# Light_Sensos.net
KiCad netlist of a schematic drawn in EAGLE
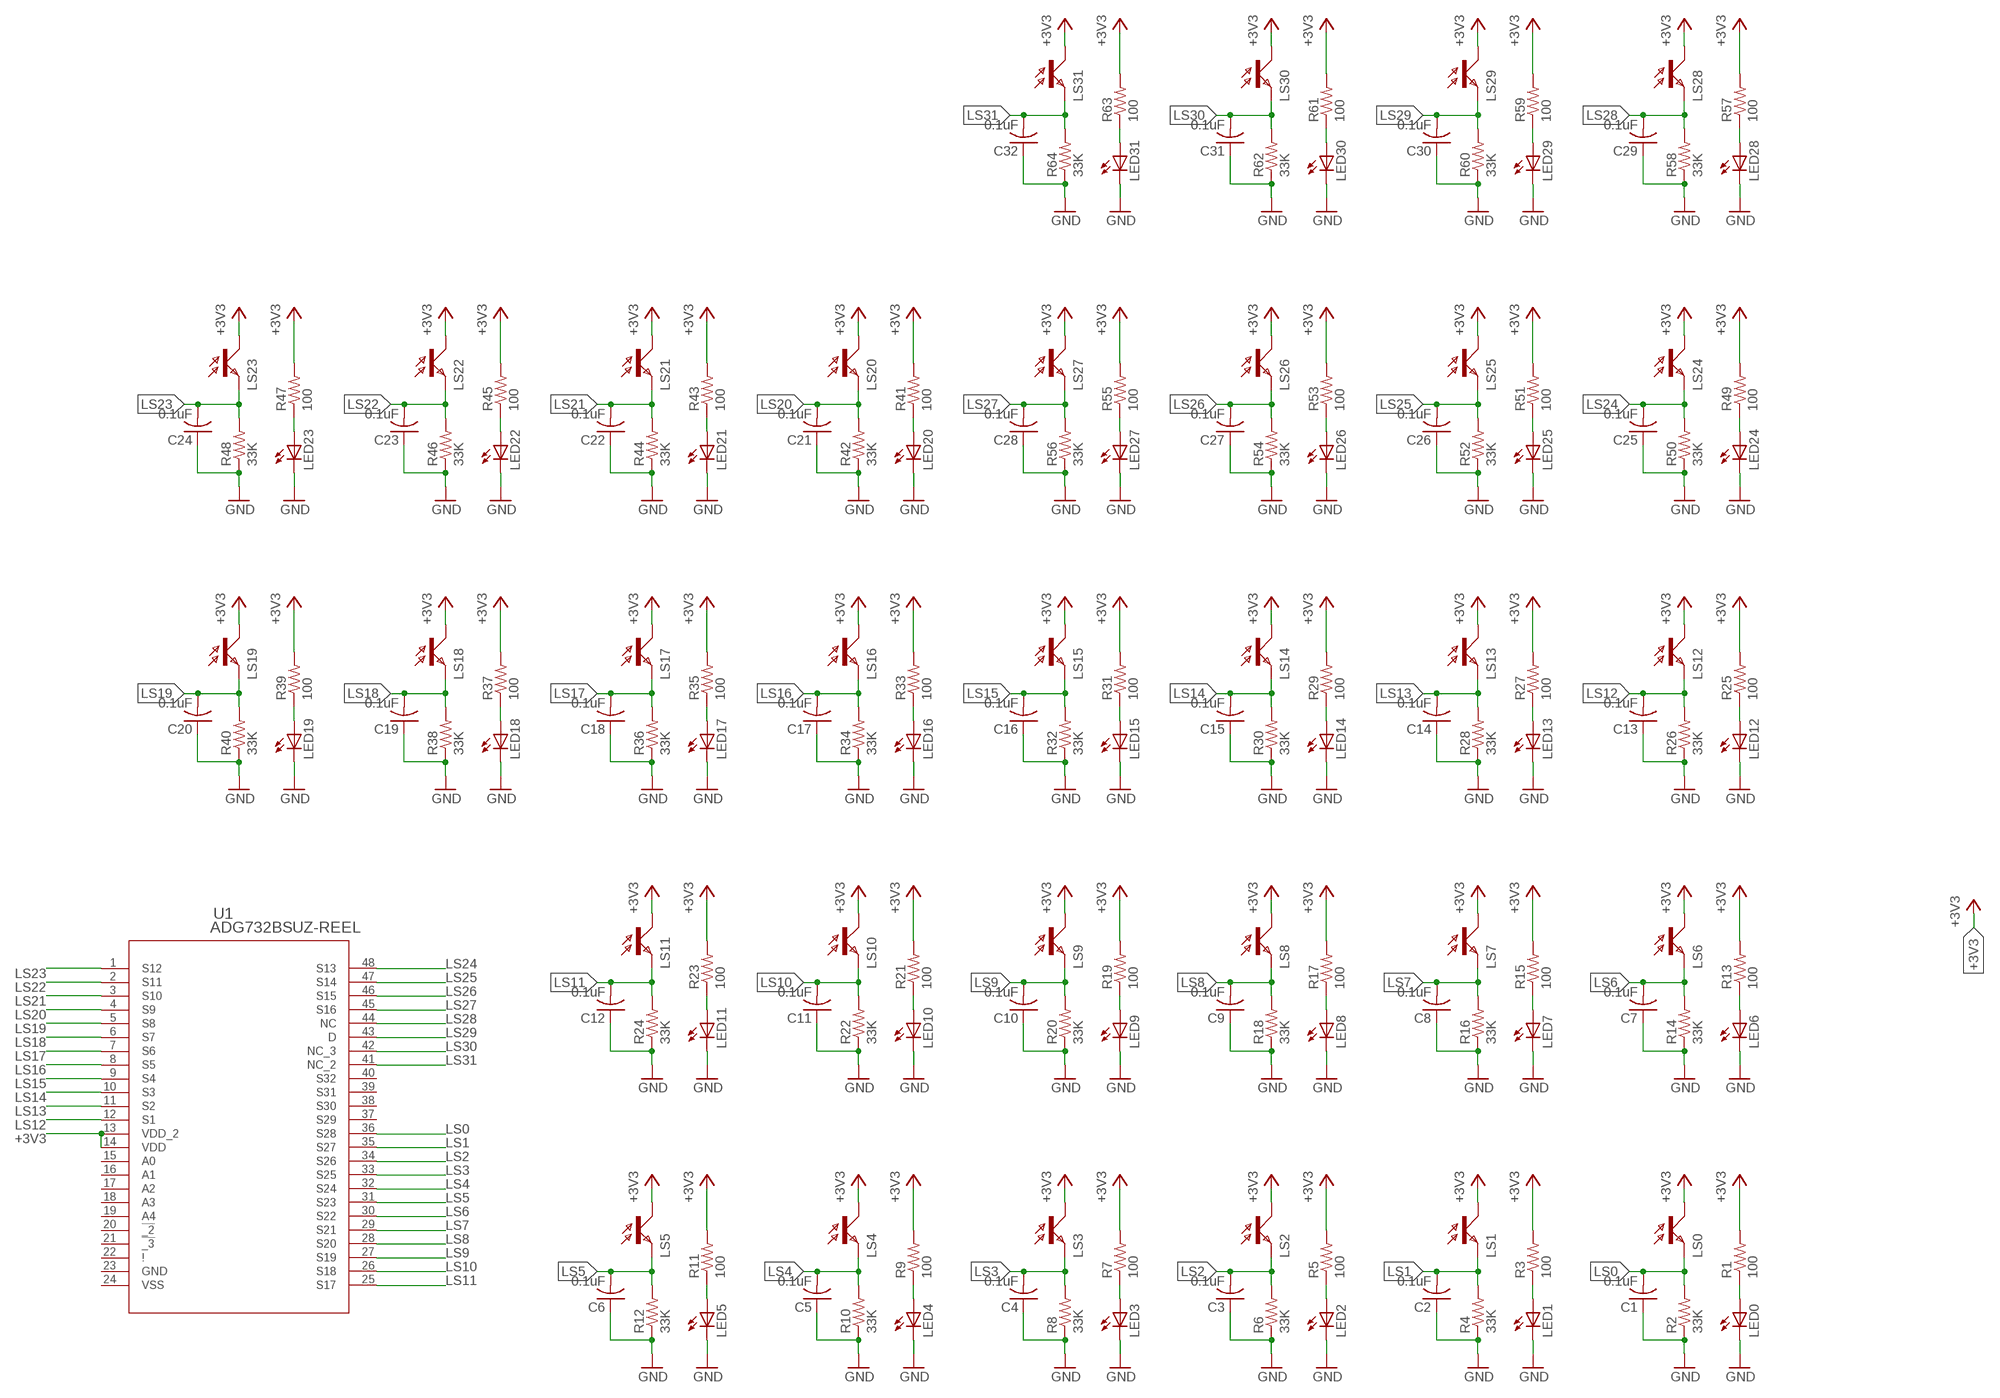
[diagram p0: schematic, sheet 1]

(export (version "E")
  (design (tool "Eeschema 10.0.6"))
  (components
    (comp (ref "C1")
      (value "0.1uF")
      (footprint "eagle-import:C0603")
      (libsource (lib "eagle-import") (part "C-USC0603"))
    )
    (comp (ref "C2")
      (value "0.1uF")
      (footprint "eagle-import:C0603")
      (libsource (lib "eagle-import") (part "C-USC0603"))
    )
    (comp (ref "C3")
      (value "0.1uF")
      (footprint "eagle-import:C0603")
      (libsource (lib "eagle-import") (part "C-USC0603"))
    )
    (comp (ref "C4")
      (value "0.1uF")
      (footprint "eagle-import:C0603")
      (libsource (lib "eagle-import") (part "C-USC0603"))
    )
    (comp (ref "C5")
      (value "0.1uF")
      (footprint "eagle-import:C0603")
      (libsource (lib "eagle-import") (part "C-USC0603"))
    )
    (comp (ref "C6")
      (value "0.1uF")
      (footprint "eagle-import:C0603")
      (libsource (lib "eagle-import") (part "C-USC0603"))
    )
    (comp (ref "C7")
      (value "0.1uF")
      (footprint "eagle-import:C0603")
      (libsource (lib "eagle-import") (part "C-USC0603"))
    )
    (comp (ref "C8")
      (value "0.1uF")
      (footprint "eagle-import:C0603")
      (libsource (lib "eagle-import") (part "C-USC0603"))
    )
    (comp (ref "C9")
      (value "0.1uF")
      (footprint "eagle-import:C0603")
      (libsource (lib "eagle-import") (part "C-USC0603"))
    )
    (comp (ref "C10")
      (value "0.1uF")
      (footprint "eagle-import:C0603")
      (libsource (lib "eagle-import") (part "C-USC0603"))
    )
    (comp (ref "C11")
      (value "0.1uF")
      (footprint "eagle-import:C0603")
      (libsource (lib "eagle-import") (part "C-USC0603"))
    )
    (comp (ref "C12")
      (value "0.1uF")
      (footprint "eagle-import:C0603")
      (libsource (lib "eagle-import") (part "C-USC0603"))
    )
    (comp (ref "C13")
      (value "0.1uF")
      (footprint "eagle-import:C0603")
      (libsource (lib "eagle-import") (part "C-USC0603"))
    )
    (comp (ref "C14")
      (value "0.1uF")
      (footprint "eagle-import:C0603")
      (libsource (lib "eagle-import") (part "C-USC0603"))
    )
    (comp (ref "C15")
      (value "0.1uF")
      (footprint "eagle-import:C0603")
      (libsource (lib "eagle-import") (part "C-USC0603"))
    )
    (comp (ref "C16")
      (value "0.1uF")
      (footprint "eagle-import:C0603")
      (libsource (lib "eagle-import") (part "C-USC0603"))
    )
    (comp (ref "C17")
      (value "0.1uF")
      (footprint "eagle-import:C0603")
      (libsource (lib "eagle-import") (part "C-USC0603"))
    )
    (comp (ref "C18")
      (value "0.1uF")
      (footprint "eagle-import:C0603")
      (libsource (lib "eagle-import") (part "C-USC0603"))
    )
    (comp (ref "C19")
      (value "0.1uF")
      (footprint "eagle-import:C0603")
      (libsource (lib "eagle-import") (part "C-USC0603"))
    )
    (comp (ref "C20")
      (value "0.1uF")
      (footprint "eagle-import:C0603")
      (libsource (lib "eagle-import") (part "C-USC0603"))
    )
    (comp (ref "C21")
      (value "0.1uF")
      (footprint "eagle-import:C0603")
      (libsource (lib "eagle-import") (part "C-USC0603"))
    )
    (comp (ref "C22")
      (value "0.1uF")
      (footprint "eagle-import:C0603")
      (libsource (lib "eagle-import") (part "C-USC0603"))
    )
    (comp (ref "C23")
      (value "0.1uF")
      (footprint "eagle-import:C0603")
      (libsource (lib "eagle-import") (part "C-USC0603"))
    )
    (comp (ref "C24")
      (value "0.1uF")
      (footprint "eagle-import:C0603")
      (libsource (lib "eagle-import") (part "C-USC0603"))
    )
    (comp (ref "C25")
      (value "0.1uF")
      (footprint "eagle-import:C0603")
      (libsource (lib "eagle-import") (part "C-USC0603"))
    )
    (comp (ref "C26")
      (value "0.1uF")
      (footprint "eagle-import:C0603")
      (libsource (lib "eagle-import") (part "C-USC0603"))
    )
    (comp (ref "C27")
      (value "0.1uF")
      (footprint "eagle-import:C0603")
      (libsource (lib "eagle-import") (part "C-USC0603"))
    )
    (comp (ref "C28")
      (value "0.1uF")
      (footprint "eagle-import:C0603")
      (libsource (lib "eagle-import") (part "C-USC0603"))
    )
    (comp (ref "C29")
      (value "0.1uF")
      (footprint "eagle-import:C0603")
      (libsource (lib "eagle-import") (part "C-USC0603"))
    )
    (comp (ref "C30")
      (value "0.1uF")
      (footprint "eagle-import:C0603")
      (libsource (lib "eagle-import") (part "C-USC0603"))
    )
    (comp (ref "C31")
      (value "0.1uF")
      (footprint "eagle-import:C0603")
      (libsource (lib "eagle-import") (part "C-USC0603"))
    )
    (comp (ref "C32")
      (value "0.1uF")
      (footprint "eagle-import:C0603")
      (libsource (lib "eagle-import") (part "C-USC0603"))
    )
    (comp (ref "LED0")
      (value "LEDCHIPLED_0603")
      (footprint "eagle-import:CHIPLED_0603")
      (libsource (lib "eagle-import") (part "LEDCHIPLED_0603"))
    )
    (comp (ref "LED1")
      (value "LEDCHIPLED_0603")
      (footprint "eagle-import:CHIPLED_0603")
      (libsource (lib "eagle-import") (part "LEDCHIPLED_0603"))
    )
    (comp (ref "LED2")
      (value "LEDCHIPLED_0603")
      (footprint "eagle-import:CHIPLED_0603")
      (libsource (lib "eagle-import") (part "LEDCHIPLED_0603"))
    )
    (comp (ref "LED3")
      (value "LEDCHIPLED_0603")
      (footprint "eagle-import:CHIPLED_0603")
      (libsource (lib "eagle-import") (part "LEDCHIPLED_0603"))
    )
    (comp (ref "LED4")
      (value "LEDCHIPLED_0603")
      (footprint "eagle-import:CHIPLED_0603")
      (libsource (lib "eagle-import") (part "LEDCHIPLED_0603"))
    )
    (comp (ref "LED5")
      (value "LEDCHIPLED_0603")
      (footprint "eagle-import:CHIPLED_0603")
      (libsource (lib "eagle-import") (part "LEDCHIPLED_0603"))
    )
    (comp (ref "LED6")
      (value "LEDCHIPLED_0603")
      (footprint "eagle-import:CHIPLED_0603")
      (libsource (lib "eagle-import") (part "LEDCHIPLED_0603"))
    )
    (comp (ref "LED7")
      (value "LEDCHIPLED_0603")
      (footprint "eagle-import:CHIPLED_0603")
      (libsource (lib "eagle-import") (part "LEDCHIPLED_0603"))
    )
    (comp (ref "LED8")
      (value "LEDCHIPLED_0603")
      (footprint "eagle-import:CHIPLED_0603")
      (libsource (lib "eagle-import") (part "LEDCHIPLED_0603"))
    )
    (comp (ref "LED9")
      (value "LEDCHIPLED_0603")
      (footprint "eagle-import:CHIPLED_0603")
      (libsource (lib "eagle-import") (part "LEDCHIPLED_0603"))
    )
    (comp (ref "LED10")
      (value "LEDCHIPLED_0603")
      (footprint "eagle-import:CHIPLED_0603")
      (libsource (lib "eagle-import") (part "LEDCHIPLED_0603"))
    )
    (comp (ref "LED11")
      (value "LEDCHIPLED_0603")
      (footprint "eagle-import:CHIPLED_0603")
      (libsource (lib "eagle-import") (part "LEDCHIPLED_0603"))
    )
    (comp (ref "LED12")
      (value "LEDCHIPLED_0603")
      (footprint "eagle-import:CHIPLED_0603")
      (libsource (lib "eagle-import") (part "LEDCHIPLED_0603"))
    )
    (comp (ref "LED13")
      (value "LEDCHIPLED_0603")
      (footprint "eagle-import:CHIPLED_0603")
      (libsource (lib "eagle-import") (part "LEDCHIPLED_0603"))
    )
    (comp (ref "LED14")
      (value "LEDCHIPLED_0603")
      (footprint "eagle-import:CHIPLED_0603")
      (libsource (lib "eagle-import") (part "LEDCHIPLED_0603"))
    )
    (comp (ref "LED15")
      (value "LEDCHIPLED_0603")
      (footprint "eagle-import:CHIPLED_0603")
      (libsource (lib "eagle-import") (part "LEDCHIPLED_0603"))
    )
    (comp (ref "LED16")
      (value "LEDCHIPLED_0603")
      (footprint "eagle-import:CHIPLED_0603")
      (libsource (lib "eagle-import") (part "LEDCHIPLED_0603"))
    )
    (comp (ref "LED17")
      (value "LEDCHIPLED_0603")
      (footprint "eagle-import:CHIPLED_0603")
      (libsource (lib "eagle-import") (part "LEDCHIPLED_0603"))
    )
    (comp (ref "LED18")
      (value "LEDCHIPLED_0603")
      (footprint "eagle-import:CHIPLED_0603")
      (libsource (lib "eagle-import") (part "LEDCHIPLED_0603"))
    )
    (comp (ref "LED19")
      (value "LEDCHIPLED_0603")
      (footprint "eagle-import:CHIPLED_0603")
      (libsource (lib "eagle-import") (part "LEDCHIPLED_0603"))
    )
    (comp (ref "LED20")
      (value "LEDCHIPLED_0603")
      (footprint "eagle-import:CHIPLED_0603")
      (libsource (lib "eagle-import") (part "LEDCHIPLED_0603"))
    )
    (comp (ref "LED21")
      (value "LEDCHIPLED_0603")
      (footprint "eagle-import:CHIPLED_0603")
      (libsource (lib "eagle-import") (part "LEDCHIPLED_0603"))
    )
    (comp (ref "LED22")
      (value "LEDCHIPLED_0603")
      (footprint "eagle-import:CHIPLED_0603")
      (libsource (lib "eagle-import") (part "LEDCHIPLED_0603"))
    )
    (comp (ref "LED23")
      (value "LEDCHIPLED_0603")
      (footprint "eagle-import:CHIPLED_0603")
      (libsource (lib "eagle-import") (part "LEDCHIPLED_0603"))
    )
    (comp (ref "LED24")
      (value "LEDCHIPLED_0603")
      (footprint "eagle-import:CHIPLED_0603")
      (libsource (lib "eagle-import") (part "LEDCHIPLED_0603"))
    )
    (comp (ref "LED25")
      (value "LEDCHIPLED_0603")
      (footprint "eagle-import:CHIPLED_0603")
      (libsource (lib "eagle-import") (part "LEDCHIPLED_0603"))
    )
    (comp (ref "LED26")
      (value "LEDCHIPLED_0603")
      (footprint "eagle-import:CHIPLED_0603")
      (libsource (lib "eagle-import") (part "LEDCHIPLED_0603"))
    )
    (comp (ref "LED27")
      (value "LEDCHIPLED_0603")
      (footprint "eagle-import:CHIPLED_0603")
      (libsource (lib "eagle-import") (part "LEDCHIPLED_0603"))
    )
    (comp (ref "LED28")
      (value "LEDCHIPLED_0603")
      (footprint "eagle-import:CHIPLED_0603")
      (libsource (lib "eagle-import") (part "LEDCHIPLED_0603"))
    )
    (comp (ref "LED29")
      (value "LEDCHIPLED_0603")
      (footprint "eagle-import:CHIPLED_0603")
      (libsource (lib "eagle-import") (part "LEDCHIPLED_0603"))
    )
    (comp (ref "LED30")
      (value "LEDCHIPLED_0603")
      (footprint "eagle-import:CHIPLED_0603")
      (libsource (lib "eagle-import") (part "LEDCHIPLED_0603"))
    )
    (comp (ref "LED31")
      (value "LEDCHIPLED_0603")
      (footprint "eagle-import:CHIPLED_0603")
      (libsource (lib "eagle-import") (part "LEDCHIPLED_0603"))
    )
    (comp (ref "LS0")
      (value "ALS")
      (footprint "eagle-import:SMD")
      (libsource (lib "eagle-import") (part "ALS"))
    )
    (comp (ref "LS1")
      (value "ALS")
      (footprint "eagle-import:SMD")
      (libsource (lib "eagle-import") (part "ALS"))
    )
    (comp (ref "LS2")
      (value "ALS")
      (footprint "eagle-import:SMD")
      (libsource (lib "eagle-import") (part "ALS"))
    )
    (comp (ref "LS3")
      (value "ALS")
      (footprint "eagle-import:SMD")
      (libsource (lib "eagle-import") (part "ALS"))
    )
    (comp (ref "LS4")
      (value "ALS")
      (footprint "eagle-import:SMD")
      (libsource (lib "eagle-import") (part "ALS"))
    )
    (comp (ref "LS5")
      (value "ALS")
      (footprint "eagle-import:SMD")
      (libsource (lib "eagle-import") (part "ALS"))
    )
    (comp (ref "LS6")
      (value "ALS")
      (footprint "eagle-import:SMD")
      (libsource (lib "eagle-import") (part "ALS"))
    )
    (comp (ref "LS7")
      (value "ALS")
      (footprint "eagle-import:SMD")
      (libsource (lib "eagle-import") (part "ALS"))
    )
    (comp (ref "LS8")
      (value "ALS")
      (footprint "eagle-import:SMD")
      (libsource (lib "eagle-import") (part "ALS"))
    )
    (comp (ref "LS9")
      (value "ALS")
      (footprint "eagle-import:SMD")
      (libsource (lib "eagle-import") (part "ALS"))
    )
    (comp (ref "LS10")
      (value "ALS")
      (footprint "eagle-import:SMD")
      (libsource (lib "eagle-import") (part "ALS"))
    )
    (comp (ref "LS11")
      (value "ALS")
      (footprint "eagle-import:SMD")
      (libsource (lib "eagle-import") (part "ALS"))
    )
    (comp (ref "LS12")
      (value "ALS")
      (footprint "eagle-import:SMD")
      (libsource (lib "eagle-import") (part "ALS"))
    )
    (comp (ref "LS13")
      (value "ALS")
      (footprint "eagle-import:SMD")
      (libsource (lib "eagle-import") (part "ALS"))
    )
    (comp (ref "LS14")
      (value "ALS")
      (footprint "eagle-import:SMD")
      (libsource (lib "eagle-import") (part "ALS"))
    )
    (comp (ref "LS15")
      (value "ALS")
      (footprint "eagle-import:SMD")
      (libsource (lib "eagle-import") (part "ALS"))
    )
    (comp (ref "LS16")
      (value "ALS")
      (footprint "eagle-import:SMD")
      (libsource (lib "eagle-import") (part "ALS"))
    )
    (comp (ref "LS17")
      (value "ALS")
      (footprint "eagle-import:SMD")
      (libsource (lib "eagle-import") (part "ALS"))
    )
    (comp (ref "LS18")
      (value "ALS")
      (footprint "eagle-import:SMD")
      (libsource (lib "eagle-import") (part "ALS"))
    )
    (comp (ref "LS19")
      (value "ALS")
      (footprint "eagle-import:SMD")
      (libsource (lib "eagle-import") (part "ALS"))
    )
    (comp (ref "LS20")
      (value "ALS")
      (footprint "eagle-import:SMD")
      (libsource (lib "eagle-import") (part "ALS"))
    )
    (comp (ref "LS21")
      (value "ALS")
      (footprint "eagle-import:SMD")
      (libsource (lib "eagle-import") (part "ALS"))
    )
    (comp (ref "LS22")
      (value "ALS")
      (footprint "eagle-import:SMD")
      (libsource (lib "eagle-import") (part "ALS"))
    )
    (comp (ref "LS23")
      (value "ALS")
      (footprint "eagle-import:SMD")
      (libsource (lib "eagle-import") (part "ALS"))
    )
    (comp (ref "LS24")
      (value "ALS")
      (footprint "eagle-import:SMD")
      (libsource (lib "eagle-import") (part "ALS"))
    )
    (comp (ref "LS25")
      (value "ALS")
      (footprint "eagle-import:SMD")
      (libsource (lib "eagle-import") (part "ALS"))
    )
    (comp (ref "LS26")
      (value "ALS")
      (footprint "eagle-import:SMD")
      (libsource (lib "eagle-import") (part "ALS"))
    )
    (comp (ref "LS27")
      (value "ALS")
      (footprint "eagle-import:SMD")
      (libsource (lib "eagle-import") (part "ALS"))
    )
    (comp (ref "LS28")
      (value "ALS")
      (footprint "eagle-import:SMD")
      (libsource (lib "eagle-import") (part "ALS"))
    )
    (comp (ref "LS29")
      (value "ALS")
      (footprint "eagle-import:SMD")
      (libsource (lib "eagle-import") (part "ALS"))
    )
    (comp (ref "LS30")
      (value "ALS")
      (footprint "eagle-import:SMD")
      (libsource (lib "eagle-import") (part "ALS"))
    )
    (comp (ref "LS31")
      (value "ALS")
      (footprint "eagle-import:SMD")
      (libsource (lib "eagle-import") (part "ALS"))
    )
    (comp (ref "R1")
      (value "100")
      (footprint "eagle-import:R0603")
      (libsource (lib "eagle-import") (part "R-US_R0603"))
    )
    (comp (ref "R2")
      (value "33K")
      (footprint "eagle-import:R0603")
      (libsource (lib "eagle-import") (part "R-US_R0603"))
    )
    (comp (ref "R3")
      (value "100")
      (footprint "eagle-import:R0603")
      (libsource (lib "eagle-import") (part "R-US_R0603"))
    )
    (comp (ref "R4")
      (value "33K")
      (footprint "eagle-import:R0603")
      (libsource (lib "eagle-import") (part "R-US_R0603"))
    )
    (comp (ref "R5")
      (value "100")
      (footprint "eagle-import:R0603")
      (libsource (lib "eagle-import") (part "R-US_R0603"))
    )
    (comp (ref "R6")
      (value "33K")
      (footprint "eagle-import:R0603")
      (libsource (lib "eagle-import") (part "R-US_R0603"))
    )
    (comp (ref "R7")
      (value "100")
      (footprint "eagle-import:R0603")
      (libsource (lib "eagle-import") (part "R-US_R0603"))
    )
    (comp (ref "R8")
      (value "33K")
      (footprint "eagle-import:R0603")
      (libsource (lib "eagle-import") (part "R-US_R0603"))
    )
    (comp (ref "R9")
      (value "100")
      (footprint "eagle-import:R0603")
      (libsource (lib "eagle-import") (part "R-US_R0603"))
    )
    (comp (ref "R10")
      (value "33K")
      (footprint "eagle-import:R0603")
      (libsource (lib "eagle-import") (part "R-US_R0603"))
    )
    (comp (ref "R11")
      (value "100")
      (footprint "eagle-import:R0603")
      (libsource (lib "eagle-import") (part "R-US_R0603"))
    )
    (comp (ref "R12")
      (value "33K")
      (footprint "eagle-import:R0603")
      (libsource (lib "eagle-import") (part "R-US_R0603"))
    )
    (comp (ref "R13")
      (value "100")
      (footprint "eagle-import:R0603")
      (libsource (lib "eagle-import") (part "R-US_R0603"))
    )
    (comp (ref "R14")
      (value "33K")
      (footprint "eagle-import:R0603")
      (libsource (lib "eagle-import") (part "R-US_R0603"))
    )
    (comp (ref "R15")
      (value "100")
      (footprint "eagle-import:R0603")
      (libsource (lib "eagle-import") (part "R-US_R0603"))
    )
    (comp (ref "R16")
      (value "33K")
      (footprint "eagle-import:R0603")
      (libsource (lib "eagle-import") (part "R-US_R0603"))
    )
    (comp (ref "R17")
      (value "100")
      (footprint "eagle-import:R0603")
      (libsource (lib "eagle-import") (part "R-US_R0603"))
    )
    (comp (ref "R18")
      (value "33K")
      (footprint "eagle-import:R0603")
      (libsource (lib "eagle-import") (part "R-US_R0603"))
    )
    (comp (ref "R19")
      (value "100")
      (footprint "eagle-import:R0603")
      (libsource (lib "eagle-import") (part "R-US_R0603"))
    )
    (comp (ref "R20")
      (value "33K")
      (footprint "eagle-import:R0603")
      (libsource (lib "eagle-import") (part "R-US_R0603"))
    )
    (comp (ref "R21")
      (value "100")
      (footprint "eagle-import:R0603")
      (libsource (lib "eagle-import") (part "R-US_R0603"))
    )
    (comp (ref "R22")
      (value "33K")
      (footprint "eagle-import:R0603")
      (libsource (lib "eagle-import") (part "R-US_R0603"))
    )
    (comp (ref "R23")
      (value "100")
      (footprint "eagle-import:R0603")
      (libsource (lib "eagle-import") (part "R-US_R0603"))
    )
    (comp (ref "R24")
      (value "33K")
      (footprint "eagle-import:R0603")
      (libsource (lib "eagle-import") (part "R-US_R0603"))
    )
    (comp (ref "R25")
      (value "100")
      (footprint "eagle-import:R0603")
      (libsource (lib "eagle-import") (part "R-US_R0603"))
    )
    (comp (ref "R26")
      (value "33K")
      (footprint "eagle-import:R0603")
      (libsource (lib "eagle-import") (part "R-US_R0603"))
    )
    (comp (ref "R27")
      (value "100")
      (footprint "eagle-import:R0603")
      (libsource (lib "eagle-import") (part "R-US_R0603"))
    )
    (comp (ref "R28")
      (value "33K")
      (footprint "eagle-import:R0603")
      (libsource (lib "eagle-import") (part "R-US_R0603"))
    )
    (comp (ref "R29")
      (value "100")
      (footprint "eagle-import:R0603")
      (libsource (lib "eagle-import") (part "R-US_R0603"))
    )
    (comp (ref "R30")
      (value "33K")
      (footprint "eagle-import:R0603")
      (libsource (lib "eagle-import") (part "R-US_R0603"))
    )
    (comp (ref "R31")
      (value "100")
      (footprint "eagle-import:R0603")
      (libsource (lib "eagle-import") (part "R-US_R0603"))
    )
    (comp (ref "R32")
      (value "33K")
      (footprint "eagle-import:R0603")
      (libsource (lib "eagle-import") (part "R-US_R0603"))
    )
    (comp (ref "R33")
      (value "100")
      (footprint "eagle-import:R0603")
      (libsource (lib "eagle-import") (part "R-US_R0603"))
    )
    (comp (ref "R34")
      (value "33K")
      (footprint "eagle-import:R0603")
      (libsource (lib "eagle-import") (part "R-US_R0603"))
    )
    (comp (ref "R35")
      (value "100")
      (footprint "eagle-import:R0603")
      (libsource (lib "eagle-import") (part "R-US_R0603"))
    )
    (comp (ref "R36")
      (value "33K")
      (footprint "eagle-import:R0603")
      (libsource (lib "eagle-import") (part "R-US_R0603"))
    )
    (comp (ref "R37")
      (value "100")
      (footprint "eagle-import:R0603")
      (libsource (lib "eagle-import") (part "R-US_R0603"))
    )
    (comp (ref "R38")
      (value "33K")
      (footprint "eagle-import:R0603")
      (libsource (lib "eagle-import") (part "R-US_R0603"))
    )
    (comp (ref "R39")
      (value "100")
      (footprint "eagle-import:R0603")
      (libsource (lib "eagle-import") (part "R-US_R0603"))
    )
    (comp (ref "R40")
      (value "33K")
      (footprint "eagle-import:R0603")
      (libsource (lib "eagle-import") (part "R-US_R0603"))
    )
    (comp (ref "R41")
      (value "100")
      (footprint "eagle-import:R0603")
      (libsource (lib "eagle-import") (part "R-US_R0603"))
    )
    (comp (ref "R42")
      (value "33K")
      (footprint "eagle-import:R0603")
      (libsource (lib "eagle-import") (part "R-US_R0603"))
    )
    (comp (ref "R43")
      (value "100")
      (footprint "eagle-import:R0603")
      (libsource (lib "eagle-import") (part "R-US_R0603"))
    )
    (comp (ref "R44")
      (value "33K")
      (footprint "eagle-import:R0603")
      (libsource (lib "eagle-import") (part "R-US_R0603"))
    )
    (comp (ref "R45")
      (value "100")
      (footprint "eagle-import:R0603")
      (libsource (lib "eagle-import") (part "R-US_R0603"))
    )
    (comp (ref "R46")
      (value "33K")
      (footprint "eagle-import:R0603")
      (libsource (lib "eagle-import") (part "R-US_R0603"))
    )
    (comp (ref "R47")
      (value "100")
      (footprint "eagle-import:R0603")
      (libsource (lib "eagle-import") (part "R-US_R0603"))
    )
    (comp (ref "R48")
      (value "33K")
      (footprint "eagle-import:R0603")
      (libsource (lib "eagle-import") (part "R-US_R0603"))
    )
    (comp (ref "R49")
      (value "100")
      (footprint "eagle-import:R0603")
      (libsource (lib "eagle-import") (part "R-US_R0603"))
    )
    (comp (ref "R50")
      (value "33K")
      (footprint "eagle-import:R0603")
      (libsource (lib "eagle-import") (part "R-US_R0603"))
    )
    (comp (ref "R51")
      (value "100")
      (footprint "eagle-import:R0603")
      (libsource (lib "eagle-import") (part "R-US_R0603"))
    )
    (comp (ref "R52")
      (value "33K")
      (footprint "eagle-import:R0603")
      (libsource (lib "eagle-import") (part "R-US_R0603"))
    )
    (comp (ref "R53")
      (value "100")
      (footprint "eagle-import:R0603")
      (libsource (lib "eagle-import") (part "R-US_R0603"))
    )
    (comp (ref "R54")
      (value "33K")
      (footprint "eagle-import:R0603")
      (libsource (lib "eagle-import") (part "R-US_R0603"))
    )
    (comp (ref "R55")
      (value "100")
      (footprint "eagle-import:R0603")
      (libsource (lib "eagle-import") (part "R-US_R0603"))
    )
    (comp (ref "R56")
      (value "33K")
      (footprint "eagle-import:R0603")
      (libsource (lib "eagle-import") (part "R-US_R0603"))
    )
    (comp (ref "R57")
      (value "100")
      (footprint "eagle-import:R0603")
      (libsource (lib "eagle-import") (part "R-US_R0603"))
    )
    (comp (ref "R58")
      (value "33K")
      (footprint "eagle-import:R0603")
      (libsource (lib "eagle-import") (part "R-US_R0603"))
    )
    (comp (ref "R59")
      (value "100")
      (footprint "eagle-import:R0603")
      (libsource (lib "eagle-import") (part "R-US_R0603"))
    )
    (comp (ref "R60")
      (value "33K")
      (footprint "eagle-import:R0603")
      (libsource (lib "eagle-import") (part "R-US_R0603"))
    )
    (comp (ref "R61")
      (value "100")
      (footprint "eagle-import:R0603")
      (libsource (lib "eagle-import") (part "R-US_R0603"))
    )
    (comp (ref "R62")
      (value "33K")
      (footprint "eagle-import:R0603")
      (libsource (lib "eagle-import") (part "R-US_R0603"))
    )
    (comp (ref "R63")
      (value "100")
      (footprint "eagle-import:R0603")
      (libsource (lib "eagle-import") (part "R-US_R0603"))
    )
    (comp (ref "R64")
      (value "33K")
      (footprint "eagle-import:R0603")
      (libsource (lib "eagle-import") (part "R-US_R0603"))
    )
    (comp (ref "U1")
      (value "ADG732BSUZ-REEL")
      (footprint "eagle-import:SU_48")
      (fields (field (name "MANUFACTURER_PART_NUMBER") "ADG732BSUZREEL"))
      (libsource (lib "eagle-import") (part "ADG732BSUZ-REEL"))
    )
  )
  (nets
    (net (code "1") (name "+3V3") (class "Default")
      (node (ref "LS0") (pin "C") (pinfunction "C_C") (pintype "passive"))
      (node (ref "LS1") (pin "C") (pinfunction "C_C") (pintype "passive"))
      (node (ref "LS10") (pin "C") (pinfunction "C_C") (pintype "passive"))
      (node (ref "LS11") (pin "C") (pinfunction "C_C") (pintype "passive"))
      (node (ref "LS12") (pin "C") (pinfunction "C_C") (pintype "passive"))
      (node (ref "LS13") (pin "C") (pinfunction "C_C") (pintype "passive"))
      (node (ref "LS14") (pin "C") (pinfunction "C_C") (pintype "passive"))
      (node (ref "LS15") (pin "C") (pinfunction "C_C") (pintype "passive"))
      (node (ref "LS16") (pin "C") (pinfunction "C_C") (pintype "passive"))
      (node (ref "LS17") (pin "C") (pinfunction "C_C") (pintype "passive"))
      (node (ref "LS18") (pin "C") (pinfunction "C_C") (pintype "passive"))
      (node (ref "LS19") (pin "C") (pinfunction "C_C") (pintype "passive"))
      (node (ref "LS2") (pin "C") (pinfunction "C_C") (pintype "passive"))
      (node (ref "LS20") (pin "C") (pinfunction "C_C") (pintype "passive"))
      (node (ref "LS21") (pin "C") (pinfunction "C_C") (pintype "passive"))
      (node (ref "LS22") (pin "C") (pinfunction "C_C") (pintype "passive"))
      (node (ref "LS23") (pin "C") (pinfunction "C_C") (pintype "passive"))
      (node (ref "LS24") (pin "C") (pinfunction "C_C") (pintype "passive"))
      (node (ref "LS25") (pin "C") (pinfunction "C_C") (pintype "passive"))
      (node (ref "LS26") (pin "C") (pinfunction "C_C") (pintype "passive"))
      (node (ref "LS27") (pin "C") (pinfunction "C_C") (pintype "passive"))
      (node (ref "LS28") (pin "C") (pinfunction "C_C") (pintype "passive"))
      (node (ref "LS29") (pin "C") (pinfunction "C_C") (pintype "passive"))
      (node (ref "LS3") (pin "C") (pinfunction "C_C") (pintype "passive"))
      (node (ref "LS30") (pin "C") (pinfunction "C_C") (pintype "passive"))
      (node (ref "LS31") (pin "C") (pinfunction "C_C") (pintype "passive"))
      (node (ref "LS4") (pin "C") (pinfunction "C_C") (pintype "passive"))
      (node (ref "LS5") (pin "C") (pinfunction "C_C") (pintype "passive"))
      (node (ref "LS6") (pin "C") (pinfunction "C_C") (pintype "passive"))
      (node (ref "LS7") (pin "C") (pinfunction "C_C") (pintype "passive"))
      (node (ref "LS8") (pin "C") (pinfunction "C_C") (pintype "passive"))
      (node (ref "LS9") (pin "C") (pinfunction "C_C") (pintype "passive"))
      (node (ref "R1") (pin "2") (pinfunction "2_2") (pintype "passive"))
      (node (ref "R11") (pin "2") (pinfunction "2_2") (pintype "passive"))
      (node (ref "R13") (pin "2") (pinfunction "2_2") (pintype "passive"))
      (node (ref "R15") (pin "2") (pinfunction "2_2") (pintype "passive"))
      (node (ref "R17") (pin "2") (pinfunction "2_2") (pintype "passive"))
      (node (ref "R19") (pin "2") (pinfunction "2_2") (pintype "passive"))
      (node (ref "R21") (pin "2") (pinfunction "2_2") (pintype "passive"))
      (node (ref "R23") (pin "2") (pinfunction "2_2") (pintype "passive"))
      (node (ref "R25") (pin "2") (pinfunction "2_2") (pintype "passive"))
      (node (ref "R27") (pin "2") (pinfunction "2_2") (pintype "passive"))
      (node (ref "R29") (pin "2") (pinfunction "2_2") (pintype "passive"))
      (node (ref "R3") (pin "2") (pinfunction "2_2") (pintype "passive"))
      (node (ref "R31") (pin "2") (pinfunction "2_2") (pintype "passive"))
      (node (ref "R33") (pin "2") (pinfunction "2_2") (pintype "passive"))
      (node (ref "R35") (pin "2") (pinfunction "2_2") (pintype "passive"))
      (node (ref "R37") (pin "2") (pinfunction "2_2") (pintype "passive"))
      (node (ref "R39") (pin "2") (pinfunction "2_2") (pintype "passive"))
      (node (ref "R41") (pin "2") (pinfunction "2_2") (pintype "passive"))
      (node (ref "R43") (pin "2") (pinfunction "2_2") (pintype "passive"))
      (node (ref "R45") (pin "2") (pinfunction "2_2") (pintype "passive"))
      (node (ref "R47") (pin "2") (pinfunction "2_2") (pintype "passive"))
      (node (ref "R49") (pin "2") (pinfunction "2_2") (pintype "passive"))
      (node (ref "R5") (pin "2") (pinfunction "2_2") (pintype "passive"))
      (node (ref "R51") (pin "2") (pinfunction "2_2") (pintype "passive"))
      (node (ref "R53") (pin "2") (pinfunction "2_2") (pintype "passive"))
      (node (ref "R55") (pin "2") (pinfunction "2_2") (pintype "passive"))
      (node (ref "R57") (pin "2") (pinfunction "2_2") (pintype "passive"))
      (node (ref "R59") (pin "2") (pinfunction "2_2") (pintype "passive"))
      (node (ref "R61") (pin "2") (pinfunction "2_2") (pintype "passive"))
      (node (ref "R63") (pin "2") (pinfunction "2_2") (pintype "passive"))
      (node (ref "R7") (pin "2") (pinfunction "2_2") (pintype "passive"))
      (node (ref "R9") (pin "2") (pinfunction "2_2") (pintype "passive"))
      (node (ref "U1") (pin "13") (pinfunction "VDD_2_13") (pintype "power_in"))
      (node (ref "U1") (pin "14") (pinfunction "VDD_14") (pintype "power_in"))
    )
    (net (code "2") (name "/VSS") (class "Default")
      (node (ref "U1") (pin "24") (pinfunction "VSS_24") (pintype "power_in"))
    )
    (net (code "3") (name "GND") (class "Default")
      (node (ref "C1") (pin "1") (pinfunction "1_1") (pintype "passive"))
      (node (ref "C10") (pin "1") (pinfunction "1_1") (pintype "passive"))
      (node (ref "C11") (pin "1") (pinfunction "1_1") (pintype "passive"))
      (node (ref "C12") (pin "1") (pinfunction "1_1") (pintype "passive"))
      (node (ref "C13") (pin "1") (pinfunction "1_1") (pintype "passive"))
      (node (ref "C14") (pin "1") (pinfunction "1_1") (pintype "passive"))
      (node (ref "C15") (pin "1") (pinfunction "1_1") (pintype "passive"))
      (node (ref "C16") (pin "1") (pinfunction "1_1") (pintype "passive"))
      (node (ref "C17") (pin "1") (pinfunction "1_1") (pintype "passive"))
      (node (ref "C18") (pin "1") (pinfunction "1_1") (pintype "passive"))
      (node (ref "C19") (pin "1") (pinfunction "1_1") (pintype "passive"))
      (node (ref "C2") (pin "1") (pinfunction "1_1") (pintype "passive"))
      (node (ref "C20") (pin "1") (pinfunction "1_1") (pintype "passive"))
      (node (ref "C21") (pin "1") (pinfunction "1_1") (pintype "passive"))
      (node (ref "C22") (pin "1") (pinfunction "1_1") (pintype "passive"))
      (node (ref "C23") (pin "1") (pinfunction "1_1") (pintype "passive"))
      (node (ref "C24") (pin "1") (pinfunction "1_1") (pintype "passive"))
      (node (ref "C25") (pin "1") (pinfunction "1_1") (pintype "passive"))
      (node (ref "C26") (pin "1") (pinfunction "1_1") (pintype "passive"))
      (node (ref "C27") (pin "1") (pinfunction "1_1") (pintype "passive"))
      (node (ref "C28") (pin "1") (pinfunction "1_1") (pintype "passive"))
      (node (ref "C29") (pin "1") (pinfunction "1_1") (pintype "passive"))
      (node (ref "C3") (pin "1") (pinfunction "1_1") (pintype "passive"))
      (node (ref "C30") (pin "1") (pinfunction "1_1") (pintype "passive"))
      (node (ref "C31") (pin "1") (pinfunction "1_1") (pintype "passive"))
      (node (ref "C32") (pin "1") (pinfunction "1_1") (pintype "passive"))
      (node (ref "C4") (pin "1") (pinfunction "1_1") (pintype "passive"))
      (node (ref "C5") (pin "1") (pinfunction "1_1") (pintype "passive"))
      (node (ref "C6") (pin "1") (pinfunction "1_1") (pintype "passive"))
      (node (ref "C7") (pin "1") (pinfunction "1_1") (pintype "passive"))
      (node (ref "C8") (pin "1") (pinfunction "1_1") (pintype "passive"))
      (node (ref "C9") (pin "1") (pinfunction "1_1") (pintype "passive"))
      (node (ref "LED0") (pin "C") (pinfunction "C_C") (pintype "passive"))
      (node (ref "LED1") (pin "C") (pinfunction "C_C") (pintype "passive"))
      (node (ref "LED10") (pin "C") (pinfunction "C_C") (pintype "passive"))
      (node (ref "LED11") (pin "C") (pinfunction "C_C") (pintype "passive"))
      (node (ref "LED12") (pin "C") (pinfunction "C_C") (pintype "passive"))
      (node (ref "LED13") (pin "C") (pinfunction "C_C") (pintype "passive"))
      (node (ref "LED14") (pin "C") (pinfunction "C_C") (pintype "passive"))
      (node (ref "LED15") (pin "C") (pinfunction "C_C") (pintype "passive"))
      (node (ref "LED16") (pin "C") (pinfunction "C_C") (pintype "passive"))
      (node (ref "LED17") (pin "C") (pinfunction "C_C") (pintype "passive"))
      (node (ref "LED18") (pin "C") (pinfunction "C_C") (pintype "passive"))
      (node (ref "LED19") (pin "C") (pinfunction "C_C") (pintype "passive"))
      (node (ref "LED2") (pin "C") (pinfunction "C_C") (pintype "passive"))
      (node (ref "LED20") (pin "C") (pinfunction "C_C") (pintype "passive"))
      (node (ref "LED21") (pin "C") (pinfunction "C_C") (pintype "passive"))
      (node (ref "LED22") (pin "C") (pinfunction "C_C") (pintype "passive"))
      (node (ref "LED23") (pin "C") (pinfunction "C_C") (pintype "passive"))
      (node (ref "LED24") (pin "C") (pinfunction "C_C") (pintype "passive"))
      (node (ref "LED25") (pin "C") (pinfunction "C_C") (pintype "passive"))
      (node (ref "LED26") (pin "C") (pinfunction "C_C") (pintype "passive"))
      (node (ref "LED27") (pin "C") (pinfunction "C_C") (pintype "passive"))
      (node (ref "LED28") (pin "C") (pinfunction "C_C") (pintype "passive"))
      (node (ref "LED29") (pin "C") (pinfunction "C_C") (pintype "passive"))
      (node (ref "LED3") (pin "C") (pinfunction "C_C") (pintype "passive"))
      (node (ref "LED30") (pin "C") (pinfunction "C_C") (pintype "passive"))
      (node (ref "LED31") (pin "C") (pinfunction "C_C") (pintype "passive"))
      (node (ref "LED4") (pin "C") (pinfunction "C_C") (pintype "passive"))
      (node (ref "LED5") (pin "C") (pinfunction "C_C") (pintype "passive"))
      (node (ref "LED6") (pin "C") (pinfunction "C_C") (pintype "passive"))
      (node (ref "LED7") (pin "C") (pinfunction "C_C") (pintype "passive"))
      (node (ref "LED8") (pin "C") (pinfunction "C_C") (pintype "passive"))
      (node (ref "LED9") (pin "C") (pinfunction "C_C") (pintype "passive"))
      (node (ref "R10") (pin "1") (pinfunction "1_1") (pintype "passive"))
      (node (ref "R12") (pin "1") (pinfunction "1_1") (pintype "passive"))
      (node (ref "R14") (pin "1") (pinfunction "1_1") (pintype "passive"))
      (node (ref "R16") (pin "1") (pinfunction "1_1") (pintype "passive"))
      (node (ref "R18") (pin "1") (pinfunction "1_1") (pintype "passive"))
      (node (ref "R2") (pin "1") (pinfunction "1_1") (pintype "passive"))
      (node (ref "R20") (pin "1") (pinfunction "1_1") (pintype "passive"))
      (node (ref "R22") (pin "1") (pinfunction "1_1") (pintype "passive"))
      (node (ref "R24") (pin "1") (pinfunction "1_1") (pintype "passive"))
      (node (ref "R26") (pin "1") (pinfunction "1_1") (pintype "passive"))
      (node (ref "R28") (pin "1") (pinfunction "1_1") (pintype "passive"))
      (node (ref "R30") (pin "1") (pinfunction "1_1") (pintype "passive"))
      (node (ref "R32") (pin "1") (pinfunction "1_1") (pintype "passive"))
      (node (ref "R34") (pin "1") (pinfunction "1_1") (pintype "passive"))
      (node (ref "R36") (pin "1") (pinfunction "1_1") (pintype "passive"))
      (node (ref "R38") (pin "1") (pinfunction "1_1") (pintype "passive"))
      (node (ref "R4") (pin "1") (pinfunction "1_1") (pintype "passive"))
      (node (ref "R40") (pin "1") (pinfunction "1_1") (pintype "passive"))
      (node (ref "R42") (pin "1") (pinfunction "1_1") (pintype "passive"))
      (node (ref "R44") (pin "1") (pinfunction "1_1") (pintype "passive"))
      (node (ref "R46") (pin "1") (pinfunction "1_1") (pintype "passive"))
      (node (ref "R48") (pin "1") (pinfunction "1_1") (pintype "passive"))
      (node (ref "R50") (pin "1") (pinfunction "1_1") (pintype "passive"))
      (node (ref "R52") (pin "1") (pinfunction "1_1") (pintype "passive"))
      (node (ref "R54") (pin "1") (pinfunction "1_1") (pintype "passive"))
      (node (ref "R56") (pin "1") (pinfunction "1_1") (pintype "passive"))
      (node (ref "R58") (pin "1") (pinfunction "1_1") (pintype "passive"))
      (node (ref "R6") (pin "1") (pinfunction "1_1") (pintype "passive"))
      (node (ref "R60") (pin "1") (pinfunction "1_1") (pintype "passive"))
      (node (ref "R62") (pin "1") (pinfunction "1_1") (pintype "passive"))
      (node (ref "R64") (pin "1") (pinfunction "1_1") (pintype "passive"))
      (node (ref "R8") (pin "1") (pinfunction "1_1") (pintype "passive"))
    )
    (net (code "4") (name "LS0") (class "Default")
      (node (ref "C1") (pin "2") (pinfunction "2_2") (pintype "passive"))
      (node (ref "LS0") (pin "E") (pinfunction "E_E") (pintype "passive"))
      (node (ref "R2") (pin "2") (pinfunction "2_2") (pintype "passive"))
      (node (ref "U1") (pin "36") (pinfunction "S28_36") (pintype "passive"))
    )
    (net (code "5") (name "LS1") (class "Default")
      (node (ref "C2") (pin "2") (pinfunction "2_2") (pintype "passive"))
      (node (ref "LS1") (pin "E") (pinfunction "E_E") (pintype "passive"))
      (node (ref "R4") (pin "2") (pinfunction "2_2") (pintype "passive"))
      (node (ref "U1") (pin "35") (pinfunction "S27_35") (pintype "passive"))
    )
    (net (code "6") (name "LS2") (class "Default")
      (node (ref "C3") (pin "2") (pinfunction "2_2") (pintype "passive"))
      (node (ref "LS2") (pin "E") (pinfunction "E_E") (pintype "passive"))
      (node (ref "R6") (pin "2") (pinfunction "2_2") (pintype "passive"))
      (node (ref "U1") (pin "34") (pinfunction "S26_34") (pintype "passive"))
    )
    (net (code "7") (name "LS3") (class "Default")
      (node (ref "C4") (pin "2") (pinfunction "2_2") (pintype "passive"))
      (node (ref "LS3") (pin "E") (pinfunction "E_E") (pintype "passive"))
      (node (ref "R8") (pin "2") (pinfunction "2_2") (pintype "passive"))
      (node (ref "U1") (pin "33") (pinfunction "S25_33") (pintype "passive"))
    )
    (net (code "8") (name "LS4") (class "Default")
      (node (ref "C5") (pin "2") (pinfunction "2_2") (pintype "passive"))
      (node (ref "LS4") (pin "E") (pinfunction "E_E") (pintype "passive"))
      (node (ref "R10") (pin "2") (pinfunction "2_2") (pintype "passive"))
      (node (ref "U1") (pin "32") (pinfunction "S24_32") (pintype "passive"))
    )
    (net (code "9") (name "LS5") (class "Default")
      (node (ref "C6") (pin "2") (pinfunction "2_2") (pintype "passive"))
      (node (ref "LS5") (pin "E") (pinfunction "E_E") (pintype "passive"))
      (node (ref "R12") (pin "2") (pinfunction "2_2") (pintype "passive"))
      (node (ref "U1") (pin "31") (pinfunction "S23_31") (pintype "passive"))
    )
    (net (code "10") (name "LS6") (class "Default")
      (node (ref "C7") (pin "2") (pinfunction "2_2") (pintype "passive"))
      (node (ref "LS6") (pin "E") (pinfunction "E_E") (pintype "passive"))
      (node (ref "R14") (pin "2") (pinfunction "2_2") (pintype "passive"))
      (node (ref "U1") (pin "30") (pinfunction "S22_30") (pintype "passive"))
    )
    (net (code "11") (name "LS7") (class "Default")
      (node (ref "C8") (pin "2") (pinfunction "2_2") (pintype "passive"))
      (node (ref "LS7") (pin "E") (pinfunction "E_E") (pintype "passive"))
      (node (ref "R16") (pin "2") (pinfunction "2_2") (pintype "passive"))
      (node (ref "U1") (pin "29") (pinfunction "S21_29") (pintype "passive"))
    )
    (net (code "12") (name "LS8") (class "Default")
      (node (ref "C9") (pin "2") (pinfunction "2_2") (pintype "passive"))
      (node (ref "LS8") (pin "E") (pinfunction "E_E") (pintype "passive"))
      (node (ref "R18") (pin "2") (pinfunction "2_2") (pintype "passive"))
      (node (ref "U1") (pin "28") (pinfunction "S20_28") (pintype "passive"))
    )
    (net (code "13") (name "LS9") (class "Default")
      (node (ref "C10") (pin "2") (pinfunction "2_2") (pintype "passive"))
      (node (ref "LS9") (pin "E") (pinfunction "E_E") (pintype "passive"))
      (node (ref "R20") (pin "2") (pinfunction "2_2") (pintype "passive"))
      (node (ref "U1") (pin "27") (pinfunction "S19_27") (pintype "passive"))
    )
    (net (code "14") (name "LS10") (class "Default")
      (node (ref "C11") (pin "2") (pinfunction "2_2") (pintype "passive"))
      (node (ref "LS10") (pin "E") (pinfunction "E_E") (pintype "passive"))
      (node (ref "R22") (pin "2") (pinfunction "2_2") (pintype "passive"))
      (node (ref "U1") (pin "26") (pinfunction "S18_26") (pintype "passive"))
    )
    (net (code "15") (name "LS11") (class "Default")
      (node (ref "C12") (pin "2") (pinfunction "2_2") (pintype "passive"))
      (node (ref "LS11") (pin "E") (pinfunction "E_E") (pintype "passive"))
      (node (ref "R24") (pin "2") (pinfunction "2_2") (pintype "passive"))
      (node (ref "U1") (pin "25") (pinfunction "S17_25") (pintype "passive"))
    )
    (net (code "16") (name "LS12") (class "Default")
      (node (ref "C13") (pin "2") (pinfunction "2_2") (pintype "passive"))
      (node (ref "LS12") (pin "E") (pinfunction "E_E") (pintype "passive"))
      (node (ref "R26") (pin "2") (pinfunction "2_2") (pintype "passive"))
      (node (ref "U1") (pin "12") (pinfunction "S1_12") (pintype "passive"))
    )
    (net (code "17") (name "LS13") (class "Default")
      (node (ref "C14") (pin "2") (pinfunction "2_2") (pintype "passive"))
      (node (ref "LS13") (pin "E") (pinfunction "E_E") (pintype "passive"))
      (node (ref "R28") (pin "2") (pinfunction "2_2") (pintype "passive"))
      (node (ref "U1") (pin "11") (pinfunction "S2_11") (pintype "passive"))
    )
    (net (code "18") (name "LS14") (class "Default")
      (node (ref "C15") (pin "2") (pinfunction "2_2") (pintype "passive"))
      (node (ref "LS14") (pin "E") (pinfunction "E_E") (pintype "passive"))
      (node (ref "R30") (pin "2") (pinfunction "2_2") (pintype "passive"))
      (node (ref "U1") (pin "10") (pinfunction "S3_10") (pintype "passive"))
    )
    (net (code "19") (name "LS15") (class "Default")
      (node (ref "C16") (pin "2") (pinfunction "2_2") (pintype "passive"))
      (node (ref "LS15") (pin "E") (pinfunction "E_E") (pintype "passive"))
      (node (ref "R32") (pin "2") (pinfunction "2_2") (pintype "passive"))
      (node (ref "U1") (pin "9") (pinfunction "S4_9") (pintype "passive"))
    )
    (net (code "20") (name "LS16") (class "Default")
      (node (ref "C17") (pin "2") (pinfunction "2_2") (pintype "passive"))
      (node (ref "LS16") (pin "E") (pinfunction "E_E") (pintype "passive"))
      (node (ref "R34") (pin "2") (pinfunction "2_2") (pintype "passive"))
      (node (ref "U1") (pin "8") (pinfunction "S5_8") (pintype "passive"))
    )
    (net (code "21") (name "LS17") (class "Default")
      (node (ref "C18") (pin "2") (pinfunction "2_2") (pintype "passive"))
      (node (ref "LS17") (pin "E") (pinfunction "E_E") (pintype "passive"))
      (node (ref "R36") (pin "2") (pinfunction "2_2") (pintype "passive"))
      (node (ref "U1") (pin "7") (pinfunction "S6_7") (pintype "passive"))
    )
    (net (code "22") (name "LS18") (class "Default")
      (node (ref "C19") (pin "2") (pinfunction "2_2") (pintype "passive"))
      (node (ref "LS18") (pin "E") (pinfunction "E_E") (pintype "passive"))
      (node (ref "R38") (pin "2") (pinfunction "2_2") (pintype "passive"))
      (node (ref "U1") (pin "6") (pinfunction "S7_6") (pintype "passive"))
    )
    (net (code "23") (name "LS19") (class "Default")
      (node (ref "C20") (pin "2") (pinfunction "2_2") (pintype "passive"))
      (node (ref "LS19") (pin "E") (pinfunction "E_E") (pintype "passive"))
      (node (ref "R40") (pin "2") (pinfunction "2_2") (pintype "passive"))
      (node (ref "U1") (pin "5") (pinfunction "S8_5") (pintype "passive"))
    )
    (net (code "24") (name "LS20") (class "Default")
      (node (ref "C21") (pin "2") (pinfunction "2_2") (pintype "passive"))
      (node (ref "LS20") (pin "E") (pinfunction "E_E") (pintype "passive"))
      (node (ref "R42") (pin "2") (pinfunction "2_2") (pintype "passive"))
      (node (ref "U1") (pin "4") (pinfunction "S9_4") (pintype "passive"))
    )
    (net (code "25") (name "LS21") (class "Default")
      (node (ref "C22") (pin "2") (pinfunction "2_2") (pintype "passive"))
      (node (ref "LS21") (pin "E") (pinfunction "E_E") (pintype "passive"))
      (node (ref "R44") (pin "2") (pinfunction "2_2") (pintype "passive"))
      (node (ref "U1") (pin "3") (pinfunction "S10_3") (pintype "passive"))
    )
    (net (code "26") (name "LS22") (class "Default")
      (node (ref "C23") (pin "2") (pinfunction "2_2") (pintype "passive"))
      (node (ref "LS22") (pin "E") (pinfunction "E_E") (pintype "passive"))
      (node (ref "R46") (pin "2") (pinfunction "2_2") (pintype "passive"))
      (node (ref "U1") (pin "2") (pinfunction "S11_2") (pintype "passive"))
    )
    (net (code "27") (name "LS23") (class "Default")
      (node (ref "C24") (pin "2") (pinfunction "2_2") (pintype "passive"))
      (node (ref "LS23") (pin "E") (pinfunction "E_E") (pintype "passive"))
      (node (ref "R48") (pin "2") (pinfunction "2_2") (pintype "passive"))
      (node (ref "U1") (pin "1") (pinfunction "S12_1") (pintype "passive"))
    )
    (net (code "28") (name "LS24") (class "Default")
      (node (ref "C25") (pin "2") (pinfunction "2_2") (pintype "passive"))
      (node (ref "LS24") (pin "E") (pinfunction "E_E") (pintype "passive"))
      (node (ref "R50") (pin "2") (pinfunction "2_2") (pintype "passive"))
      (node (ref "U1") (pin "48") (pinfunction "S13_48") (pintype "passive"))
    )
    (net (code "29") (name "LS25") (class "Default")
      (node (ref "C26") (pin "2") (pinfunction "2_2") (pintype "passive"))
      (node (ref "LS25") (pin "E") (pinfunction "E_E") (pintype "passive"))
      (node (ref "R52") (pin "2") (pinfunction "2_2") (pintype "passive"))
      (node (ref "U1") (pin "47") (pinfunction "S14_47") (pintype "passive"))
    )
    (net (code "30") (name "LS26") (class "Default")
      (node (ref "C27") (pin "2") (pinfunction "2_2") (pintype "passive"))
      (node (ref "LS26") (pin "E") (pinfunction "E_E") (pintype "passive"))
      (node (ref "R54") (pin "2") (pinfunction "2_2") (pintype "passive"))
      (node (ref "U1") (pin "46") (pinfunction "S15_46") (pintype "passive"))
    )
    (net (code "31") (name "LS27") (class "Default")
      (node (ref "C28") (pin "2") (pinfunction "2_2") (pintype "passive"))
      (node (ref "LS27") (pin "E") (pinfunction "E_E") (pintype "passive"))
      (node (ref "R56") (pin "2") (pinfunction "2_2") (pintype "passive"))
      (node (ref "U1") (pin "45") (pinfunction "S16_45") (pintype "passive"))
    )
    (net (code "32") (name "LS28") (class "Default")
      (node (ref "C29") (pin "2") (pinfunction "2_2") (pintype "passive"))
      (node (ref "LS28") (pin "E") (pinfunction "E_E") (pintype "passive"))
      (node (ref "R58") (pin "2") (pinfunction "2_2") (pintype "passive"))
      (node (ref "U1") (pin "44") (pinfunction "NC_44") (pintype "passive"))
    )
    (net (code "33") (name "LS29") (class "Default")
      (node (ref "C30") (pin "2") (pinfunction "2_2") (pintype "passive"))
      (node (ref "LS29") (pin "E") (pinfunction "E_E") (pintype "passive"))
      (node (ref "R60") (pin "2") (pinfunction "2_2") (pintype "passive"))
      (node (ref "U1") (pin "43") (pinfunction "D_43") (pintype "passive"))
    )
    (net (code "34") (name "LS30") (class "Default")
      (node (ref "C31") (pin "2") (pinfunction "2_2") (pintype "passive"))
      (node (ref "LS30") (pin "E") (pinfunction "E_E") (pintype "passive"))
      (node (ref "R62") (pin "2") (pinfunction "2_2") (pintype "passive"))
      (node (ref "U1") (pin "42") (pinfunction "NC_3_42") (pintype "passive"))
    )
    (net (code "35") (name "LS31") (class "Default")
      (node (ref "C32") (pin "2") (pinfunction "2_2") (pintype "passive"))
      (node (ref "LS31") (pin "E") (pinfunction "E_E") (pintype "passive"))
      (node (ref "R64") (pin "2") (pinfunction "2_2") (pintype "passive"))
      (node (ref "U1") (pin "41") (pinfunction "NC_2_41") (pintype "passive"))
    )
    (net (code "36") (name "Net-(LED0-PadA)") (class "Default")
      (node (ref "LED0") (pin "A") (pinfunction "A_A") (pintype "passive"))
      (node (ref "R1") (pin "1") (pinfunction "1_1") (pintype "passive"))
    )
    (net (code "37") (name "Net-(LED1-PadA)") (class "Default")
      (node (ref "LED1") (pin "A") (pinfunction "A_A") (pintype "passive"))
      (node (ref "R3") (pin "1") (pinfunction "1_1") (pintype "passive"))
    )
    (net (code "38") (name "Net-(LED2-PadA)") (class "Default")
      (node (ref "LED2") (pin "A") (pinfunction "A_A") (pintype "passive"))
      (node (ref "R5") (pin "1") (pinfunction "1_1") (pintype "passive"))
    )
    (net (code "39") (name "Net-(LED3-PadA)") (class "Default")
      (node (ref "LED3") (pin "A") (pinfunction "A_A") (pintype "passive"))
      (node (ref "R7") (pin "1") (pinfunction "1_1") (pintype "passive"))
    )
    (net (code "40") (name "Net-(LED4-PadA)") (class "Default")
      (node (ref "LED4") (pin "A") (pinfunction "A_A") (pintype "passive"))
      (node (ref "R9") (pin "1") (pinfunction "1_1") (pintype "passive"))
    )
    (net (code "41") (name "Net-(LED5-PadA)") (class "Default")
      (node (ref "LED5") (pin "A") (pinfunction "A_A") (pintype "passive"))
      (node (ref "R11") (pin "1") (pinfunction "1_1") (pintype "passive"))
    )
    (net (code "42") (name "Net-(LED6-PadA)") (class "Default")
      (node (ref "LED6") (pin "A") (pinfunction "A_A") (pintype "passive"))
      (node (ref "R13") (pin "1") (pinfunction "1_1") (pintype "passive"))
    )
    (net (code "43") (name "Net-(LED7-PadA)") (class "Default")
      (node (ref "LED7") (pin "A") (pinfunction "A_A") (pintype "passive"))
      (node (ref "R15") (pin "1") (pinfunction "1_1") (pintype "passive"))
    )
    (net (code "44") (name "Net-(LED8-PadA)") (class "Default")
      (node (ref "LED8") (pin "A") (pinfunction "A_A") (pintype "passive"))
      (node (ref "R17") (pin "1") (pinfunction "1_1") (pintype "passive"))
    )
    (net (code "45") (name "Net-(LED9-PadA)") (class "Default")
      (node (ref "LED9") (pin "A") (pinfunction "A_A") (pintype "passive"))
      (node (ref "R19") (pin "1") (pinfunction "1_1") (pintype "passive"))
    )
    (net (code "46") (name "Net-(LED10-PadA)") (class "Default")
      (node (ref "LED10") (pin "A") (pinfunction "A_A") (pintype "passive"))
      (node (ref "R21") (pin "1") (pinfunction "1_1") (pintype "passive"))
    )
    (net (code "47") (name "Net-(LED11-PadA)") (class "Default")
      (node (ref "LED11") (pin "A") (pinfunction "A_A") (pintype "passive"))
      (node (ref "R23") (pin "1") (pinfunction "1_1") (pintype "passive"))
    )
    (net (code "48") (name "Net-(LED12-PadA)") (class "Default")
      (node (ref "LED12") (pin "A") (pinfunction "A_A") (pintype "passive"))
      (node (ref "R25") (pin "1") (pinfunction "1_1") (pintype "passive"))
    )
    (net (code "49") (name "Net-(LED13-PadA)") (class "Default")
      (node (ref "LED13") (pin "A") (pinfunction "A_A") (pintype "passive"))
      (node (ref "R27") (pin "1") (pinfunction "1_1") (pintype "passive"))
    )
    (net (code "50") (name "Net-(LED14-PadA)") (class "Default")
      (node (ref "LED14") (pin "A") (pinfunction "A_A") (pintype "passive"))
      (node (ref "R29") (pin "1") (pinfunction "1_1") (pintype "passive"))
    )
    (net (code "51") (name "Net-(LED15-PadA)") (class "Default")
      (node (ref "LED15") (pin "A") (pinfunction "A_A") (pintype "passive"))
      (node (ref "R31") (pin "1") (pinfunction "1_1") (pintype "passive"))
    )
    (net (code "52") (name "Net-(LED16-PadA)") (class "Default")
      (node (ref "LED16") (pin "A") (pinfunction "A_A") (pintype "passive"))
      (node (ref "R33") (pin "1") (pinfunction "1_1") (pintype "passive"))
    )
    (net (code "53") (name "Net-(LED17-PadA)") (class "Default")
      (node (ref "LED17") (pin "A") (pinfunction "A_A") (pintype "passive"))
      (node (ref "R35") (pin "1") (pinfunction "1_1") (pintype "passive"))
    )
    (net (code "54") (name "Net-(LED18-PadA)") (class "Default")
      (node (ref "LED18") (pin "A") (pinfunction "A_A") (pintype "passive"))
      (node (ref "R37") (pin "1") (pinfunction "1_1") (pintype "passive"))
    )
    (net (code "55") (name "Net-(LED19-PadA)") (class "Default")
      (node (ref "LED19") (pin "A") (pinfunction "A_A") (pintype "passive"))
      (node (ref "R39") (pin "1") (pinfunction "1_1") (pintype "passive"))
    )
    (net (code "56") (name "Net-(LED20-PadA)") (class "Default")
      (node (ref "LED20") (pin "A") (pinfunction "A_A") (pintype "passive"))
      (node (ref "R41") (pin "1") (pinfunction "1_1") (pintype "passive"))
    )
    (net (code "57") (name "Net-(LED21-PadA)") (class "Default")
      (node (ref "LED21") (pin "A") (pinfunction "A_A") (pintype "passive"))
      (node (ref "R43") (pin "1") (pinfunction "1_1") (pintype "passive"))
    )
    (net (code "58") (name "Net-(LED22-PadA)") (class "Default")
      (node (ref "LED22") (pin "A") (pinfunction "A_A") (pintype "passive"))
      (node (ref "R45") (pin "1") (pinfunction "1_1") (pintype "passive"))
    )
    (net (code "59") (name "Net-(LED23-PadA)") (class "Default")
      (node (ref "LED23") (pin "A") (pinfunction "A_A") (pintype "passive"))
      (node (ref "R47") (pin "1") (pinfunction "1_1") (pintype "passive"))
    )
    (net (code "60") (name "Net-(LED24-PadA)") (class "Default")
      (node (ref "LED24") (pin "A") (pinfunction "A_A") (pintype "passive"))
      (node (ref "R49") (pin "1") (pinfunction "1_1") (pintype "passive"))
    )
    (net (code "61") (name "Net-(LED25-PadA)") (class "Default")
      (node (ref "LED25") (pin "A") (pinfunction "A_A") (pintype "passive"))
      (node (ref "R51") (pin "1") (pinfunction "1_1") (pintype "passive"))
    )
    (net (code "62") (name "Net-(LED26-PadA)") (class "Default")
      (node (ref "LED26") (pin "A") (pinfunction "A_A") (pintype "passive"))
      (node (ref "R53") (pin "1") (pinfunction "1_1") (pintype "passive"))
    )
    (net (code "63") (name "Net-(LED27-PadA)") (class "Default")
      (node (ref "LED27") (pin "A") (pinfunction "A_A") (pintype "passive"))
      (node (ref "R55") (pin "1") (pinfunction "1_1") (pintype "passive"))
    )
    (net (code "64") (name "Net-(LED28-PadA)") (class "Default")
      (node (ref "LED28") (pin "A") (pinfunction "A_A") (pintype "passive"))
      (node (ref "R57") (pin "1") (pinfunction "1_1") (pintype "passive"))
    )
    (net (code "65") (name "Net-(LED29-PadA)") (class "Default")
      (node (ref "LED29") (pin "A") (pinfunction "A_A") (pintype "passive"))
      (node (ref "R59") (pin "1") (pinfunction "1_1") (pintype "passive"))
    )
    (net (code "66") (name "Net-(LED30-PadA)") (class "Default")
      (node (ref "LED30") (pin "A") (pinfunction "A_A") (pintype "passive"))
      (node (ref "R61") (pin "1") (pinfunction "1_1") (pintype "passive"))
    )
    (net (code "67") (name "Net-(LED31-PadA)") (class "Default")
      (node (ref "LED31") (pin "A") (pinfunction "A_A") (pintype "passive"))
      (node (ref "R63") (pin "1") (pinfunction "1_1") (pintype "passive"))
    )
    (net (code "68") (name "unconnected-(U1-A0-Pad15)") (class "Default")
      (node (ref "U1") (pin "15") (pinfunction "A0_15") (pintype "passive"))
    )
    (net (code "69") (name "unconnected-(U1-A1-Pad16)") (class "Default")
      (node (ref "U1") (pin "16") (pinfunction "A1_16") (pintype "passive"))
    )
    (net (code "70") (name "unconnected-(U1-A2-Pad17)") (class "Default")
      (node (ref "U1") (pin "17") (pinfunction "A2_17") (pintype "passive"))
    )
    (net (code "71") (name "unconnected-(U1-A3-Pad18)") (class "Default")
      (node (ref "U1") (pin "18") (pinfunction "A3_18") (pintype "passive"))
    )
    (net (code "72") (name "unconnected-(U1-A4-Pad19)") (class "Default")
      (node (ref "U1") (pin "19") (pinfunction "A4_19") (pintype "passive"))
    )
    (net (code "73") (name "unconnected-(U1-GND-Pad23)") (class "Default")
      (node (ref "U1") (pin "23") (pinfunction "GND_23") (pintype "passive"))
    )
    (net (code "74") (name "unconnected-(U1-S29-Pad37)") (class "Default")
      (node (ref "U1") (pin "37") (pinfunction "S29_37") (pintype "passive"))
    )
    (net (code "75") (name "unconnected-(U1-S30-Pad38)") (class "Default")
      (node (ref "U1") (pin "38") (pinfunction "S30_38") (pintype "passive"))
    )
    (net (code "76") (name "unconnected-(U1-S31-Pad39)") (class "Default")
      (node (ref "U1") (pin "39") (pinfunction "S31_39") (pintype "passive"))
    )
    (net (code "77") (name "unconnected-(U1-S32-Pad40)") (class "Default")
      (node (ref "U1") (pin "40") (pinfunction "S32_40") (pintype "passive"))
    )
    (net (code "78") (name "unconnected-(U1-~-Pad22)") (class "Default")
      (node (ref "U1") (pin "22") (pinfunction "~_22") (pintype "passive"))
    )
    (net (code "79") (name "unconnected-(U1-~{_2}-Pad20)") (class "Default")
      (node (ref "U1") (pin "20") (pinfunction "~{_2}_20") (pintype "passive"))
    )
    (net (code "80") (name "unconnected-(U1-~{_3}-Pad21)") (class "Default")
      (node (ref "U1") (pin "21") (pinfunction "~{_3}_21") (pintype "passive"))
    )
  )
)
